# baseband.net
KiCad netlist of a schematic drawn in Altium Designer
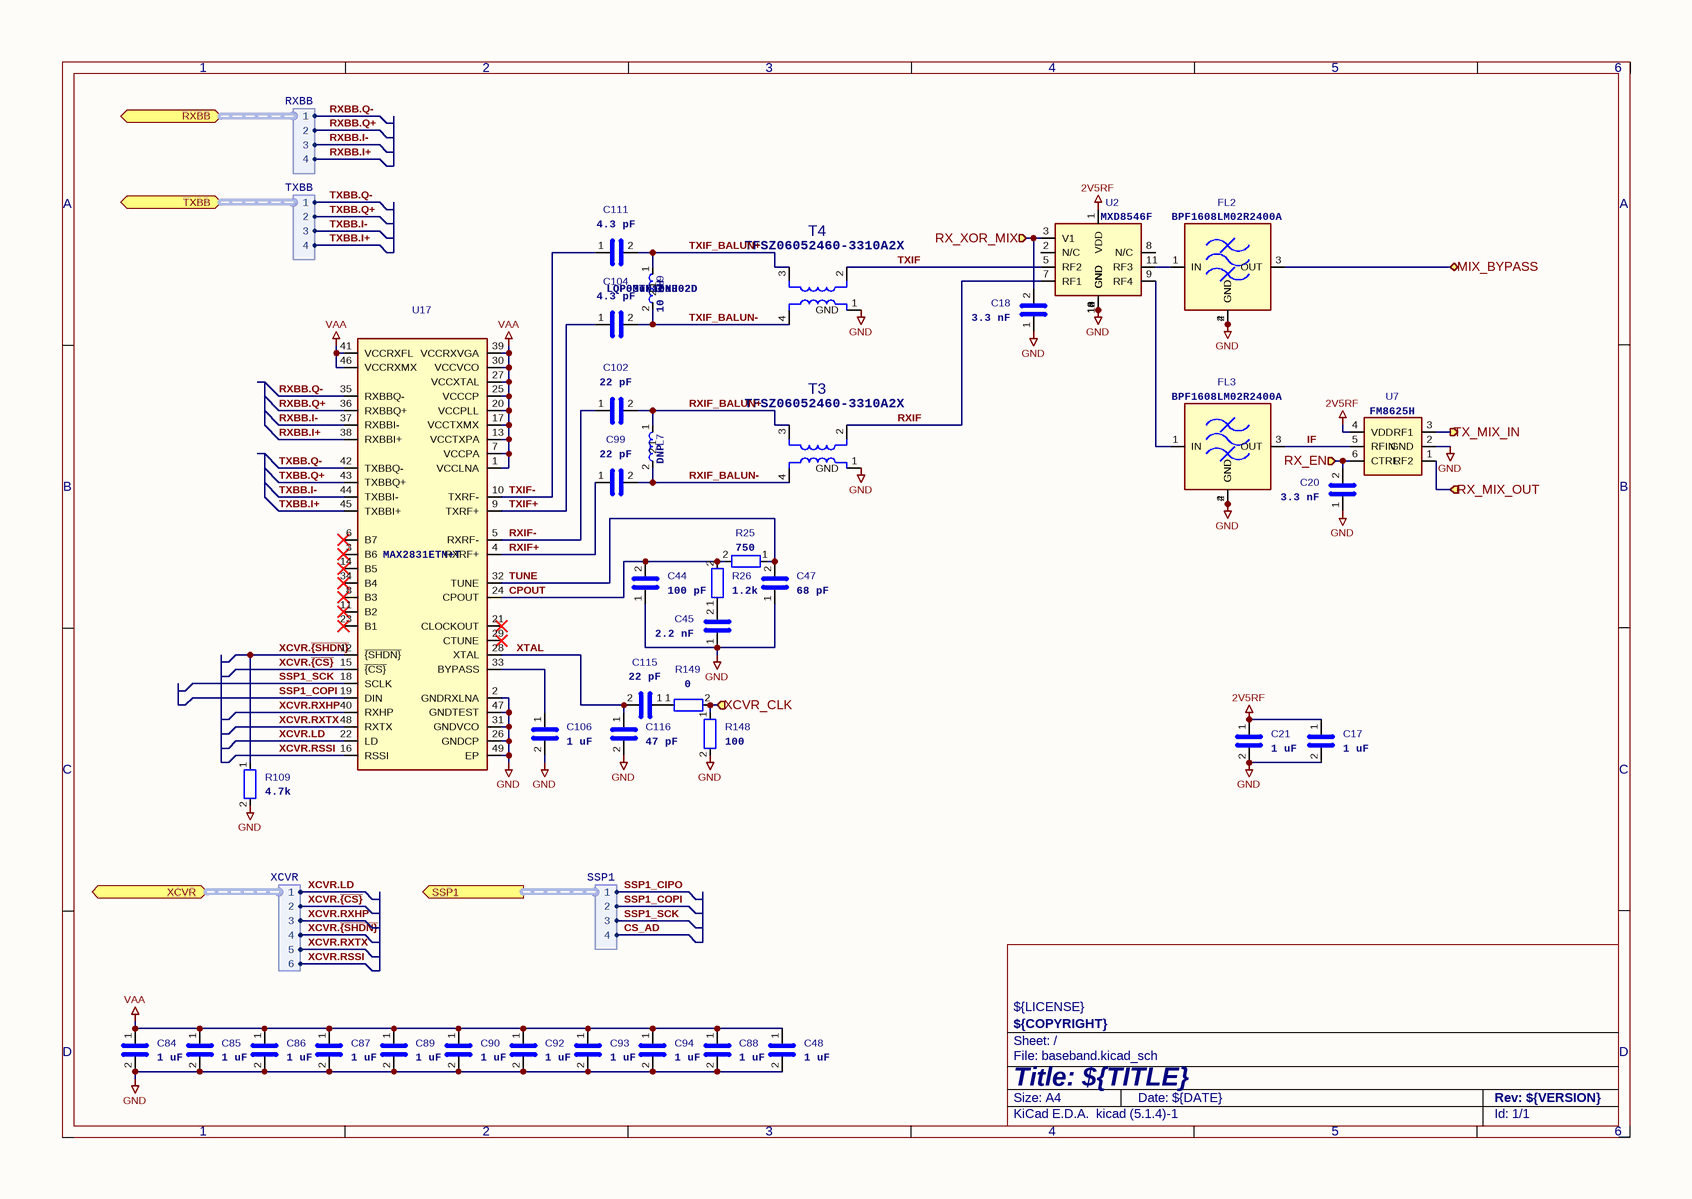
[diagram p0: baseband.SchDoc]

(export (version "E")
  (design (tool "Eeschema 10.0.6"))
  (components
    (comp (ref "C17")
      (value "1 uF")
      (footprint "C_0201_0603Metric")
      (fields (field (name "MANUFACTURER") "Murata") (field (name "PART NUMBER") "GRM033R61A105ME44D"))
      (libsource (lib "Device") (part "C"))
    )
    (comp (ref "C18")
      (value "3.3 nF")
      (footprint "C_0201_0603Metric")
      (fields (field (name "MANUFACTURER") "Murata") (field (name "PART NUMBER") "GRM033R71A332KA01D"))
      (libsource (lib "Device") (part "C"))
    )
    (comp (ref "C20")
      (value "3.3 nF")
      (footprint "C_0201_0603Metric")
      (fields (field (name "MANUFACTURER") "Murata") (field (name "PART NUMBER") "GRM033R71A332KA01D"))
      (libsource (lib "Device") (part "C"))
    )
    (comp (ref "C21")
      (value "1 uF")
      (footprint "C_0201_0603Metric")
      (fields (field (name "MANUFACTURER") "Murata") (field (name "PART NUMBER") "GRM033R61A105ME44D"))
      (libsource (lib "Device") (part "C"))
    )
    (comp (ref "C44")
      (value "100 pF")
      (footprint "C_0201_0603Metric")
      (fields (field (name "MANUFACTURER") "Murata") (field (name "PART NUMBER") "GRM0335C1E101JA01D"))
      (libsource (lib "Device") (part "C"))
    )
    (comp (ref "C45")
      (value "2.2 nF")
      (footprint "C_0201_0603Metric")
      (fields (field (name "MANUFACTURER") "Murata") (field (name "PART NUMBER") "GRM033R71A222KA01D"))
      (libsource (lib "Device") (part "C"))
    )
    (comp (ref "C47")
      (value "68 pF")
      (footprint "C_0201_0603Metric")
      (fields (field (name "MANUFACTURER") "Murata") (field (name "PART NUMBER") "GRM0335C1H680JA01D"))
      (libsource (lib "Device") (part "C"))
    )
    (comp (ref "C48")
      (value "1 uF")
      (footprint "C_0201_0603Metric")
      (fields (field (name "MANUFACTURER") "Murata") (field (name "PART NUMBER") "GRM033R61A105ME44D"))
      (libsource (lib "Device") (part "C"))
    )
    (comp (ref "C84")
      (value "1 uF")
      (footprint "C_0201_0603Metric")
      (fields (field (name "MANUFACTURER") "Murata") (field (name "PART NUMBER") "GRM033R61A105ME44D"))
      (libsource (lib "Device") (part "C"))
    )
    (comp (ref "C85")
      (value "1 uF")
      (footprint "C_0201_0603Metric")
      (fields (field (name "MANUFACTURER") "Murata") (field (name "PART NUMBER") "GRM033R61A105ME44D"))
      (libsource (lib "Device") (part "C"))
    )
    (comp (ref "C86")
      (value "1 uF")
      (footprint "C_0201_0603Metric")
      (fields (field (name "MANUFACTURER") "Murata") (field (name "PART NUMBER") "GRM033R61A105ME44D"))
      (libsource (lib "Device") (part "C"))
    )
    (comp (ref "C87")
      (value "1 uF")
      (footprint "C_0201_0603Metric")
      (fields (field (name "MANUFACTURER") "Murata") (field (name "PART NUMBER") "GRM033R61A105ME44D"))
      (libsource (lib "Device") (part "C"))
    )
    (comp (ref "C88")
      (value "1 uF")
      (footprint "C_0201_0603Metric")
      (fields (field (name "MANUFACTURER") "Murata") (field (name "PART NUMBER") "GRM033R61A105ME44D"))
      (libsource (lib "Device") (part "C"))
    )
    (comp (ref "C89")
      (value "1 uF")
      (footprint "C_0201_0603Metric")
      (fields (field (name "MANUFACTURER") "Murata") (field (name "PART NUMBER") "GRM033R61A105ME44D"))
      (libsource (lib "Device") (part "C"))
    )
    (comp (ref "C90")
      (value "1 uF")
      (footprint "C_0201_0603Metric")
      (fields (field (name "MANUFACTURER") "Murata") (field (name "PART NUMBER") "GRM033R61A105ME44D"))
      (libsource (lib "Device") (part "C"))
    )
    (comp (ref "C92")
      (value "1 uF")
      (footprint "C_0201_0603Metric")
      (fields (field (name "MANUFACTURER") "Murata") (field (name "PART NUMBER") "GRM033R61A105ME44D"))
      (libsource (lib "Device") (part "C"))
    )
    (comp (ref "C93")
      (value "1 uF")
      (footprint "C_0201_0603Metric")
      (fields (field (name "MANUFACTURER") "Murata") (field (name "PART NUMBER") "GRM033R61A105ME44D"))
      (libsource (lib "Device") (part "C"))
    )
    (comp (ref "C94")
      (value "1 uF")
      (footprint "C_0201_0603Metric")
      (fields (field (name "MANUFACTURER") "Murata") (field (name "PART NUMBER") "GRM033R61A105ME44D"))
      (libsource (lib "Device") (part "C"))
    )
    (comp (ref "C99")
      (value "22 pF")
      (footprint "C_0201_0603Metric")
      (fields (field (name "MANUFACTURER") "Murata") (field (name "PART NUMBER") "GRM0335C1H220JA01D"))
      (libsource (lib "Device") (part "C"))
    )
    (comp (ref "C102")
      (value "22 pF")
      (footprint "C_0201_0603Metric")
      (fields (field (name "MANUFACTURER") "Murata") (field (name "PART NUMBER") "GRM0335C1H220JA01D"))
      (libsource (lib "Device") (part "C"))
    )
    (comp (ref "C104")
      (value "4.3 pF")
      (footprint "C_0201_0603Metric")
      (fields (field (name "MANUFACTURER") "Murata") (field (name "PART NUMBER") "GRM0335C1E4R3CA01D"))
      (libsource (lib "Device") (part "C"))
    )
    (comp (ref "C106")
      (value "1 uF")
      (footprint "C_0201_0603Metric")
      (fields (field (name "MANUFACTURER") "Murata") (field (name "PART NUMBER") "GRM033R61A105ME44D"))
      (libsource (lib "Device") (part "C"))
    )
    (comp (ref "C111")
      (value "4.3 pF")
      (footprint "C_0201_0603Metric")
      (fields (field (name "MANUFACTURER") "Murata") (field (name "PART NUMBER") "GRM0335C1E4R3CA01D"))
      (libsource (lib "Device") (part "C"))
    )
    (comp (ref "C115")
      (value "22 pF")
      (footprint "C_0201_0603Metric")
      (fields (field (name "MANUFACTURER") "Murata") (field (name "PART NUMBER") "GRM0335C1H220JA01D"))
      (libsource (lib "Device") (part "C"))
    )
    (comp (ref "C116")
      (value "47 pF")
      (footprint "C_0201_0603Metric")
      (fields (field (name "MANUFACTURER") "Murata") (field (name "PART NUMBER") "GRM0335C1E470JA01D"))
      (libsource (lib "Device") (part "C"))
    )
    (comp (ref "FL2")
      (value "BPF")
      (footprint "Filter_Pulse_BPF1608LM09R5000A")
      (fields
        (field (name "MANUFACTURER") "Pulse Electronics")
        (field (name "PART NUMBER") "BPF1608LM02R2400A")
      )
      (libsource (lib "RF_Filter") (part "BFCN-1445"))
    )
    (comp (ref "FL3")
      (value "BPF")
      (footprint "Filter_Pulse_BPF1608LM09R5000A")
      (fields
        (field (name "MANUFACTURER") "Pulse Electronics")
        (field (name "PART NUMBER") "BPF1608LM02R2400A")
      )
      (libsource (lib "RF_Filter") (part "BFCN-1445"))
    )
    (comp (ref "L7") (value "DNP") (footprint "L_0201_0603Metric") (libsource (lib "Device") (part "L")))
    (comp (ref "L9")
      (value "10 nH")
      (footprint "L_0201_0603Metric")
      (fields
        (field (name "MANUFACTURER") "Murata")
        (field (name "PART NUMBER") "LQP03TN10NJ02D")
        (field (name "SUBSTITUTION") "LQP03TN10NH02D")
      )
      (libsource (lib "Device") (part "L"))
    )
    (comp (ref "R25")
      (value "750")
      (footprint "R_0201_0603Metric")
      (fields (field (name "MANUFACTURER") "Yageo") (field (name "PART NUMBER") "RC0201JR-07750RL"))
      (libsource (lib "Device") (part "R"))
    )
    (comp (ref "R26")
      (value "1.2k")
      (footprint "R_0201_0603Metric")
      (fields (field (name "MANUFACTURER") "Yageo") (field (name "PART NUMBER") "RC0201JR-071K2L"))
      (libsource (lib "") (part "R_1"))
    )
    (comp (ref "R109")
      (value "4.7k")
      (footprint "R_0201_0603Metric")
      (fields (field (name "MANUFACTURER") "Yageo") (field (name "PART NUMBER") "RC0201FR-074K7L"))
      (libsource (lib "Device") (part "R"))
    )
    (comp (ref "R148")
      (value "100")
      (footprint "R_0201_0603Metric")
      (fields (field (name "MANUFACTURER") "Yageo") (field (name "PART NUMBER") "RC0201JR-07100RL"))
      (libsource (lib "Device") (part "R"))
    )
    (comp (ref "R149")
      (value "0")
      (footprint "R_0201_0603Metric")
      (fields (field (name "MANUFACTURER") "Yageo") (field (name "PART NUMBER") "RC0201JR-070RL"))
      (libsource (lib "") (part "R_1"))
    )
    (comp (ref "T3")
      (value "IF_BALUN")
      (footprint "Balun_TDK_TFSZ06052460-3310A2X")
      (fields (field (name "MANUFACTURER") "TDK") (field (name "PART NUMBER") "TFSZ06052460-3310A2X"))
      (libsource (lib "praline") (part "TFSZ06052460-3310A2X"))
    )
    (comp (ref "T4")
      (value "IF_BALUN")
      (footprint "Balun_TDK_TFSZ06052460-3310A2X")
      (fields (field (name "MANUFACTURER") "TDK") (field (name "PART NUMBER") "TFSZ06052460-3310A2X"))
      (libsource (lib "praline") (part "TFSZ06052460-3310A2X"))
    )
    (comp (ref "U2")
      (value "MXD8546F")
      (footprint "QFN-12-1EP_2x2mm_P0.5mm_EP1x1mm")
      (fields (field (name "MANUFACTURER") "Maxscend") (field (name "PART NUMBER") "MXD8546F"))
      (libsource (lib "praline") (part "MXD8546F"))
    )
    (comp (ref "U7")
      (value "FM8625H")
      (footprint "TSLP-6-4_1.1x0.7mm_P0.4mm")
      (fields (field (name "MANUFACTURER") "Shenzhen Fuman") (field (name "PART NUMBER") "FM8625H"))
      (libsource (lib "praline") (part "BGS12P2L6"))
    )
    (comp (ref "U17")
      (value "MAX2831")
      (footprint "QFN-48-1EP_7x7mm_P0.5mm_EP5.6x5.6mm_ThermalVias")
      (fields (field (name "MANUFACTURER") "Maxim") (field (name "PART NUMBER") "MAX2831ETM+T"))
      (libsource (lib "praline") (part "MAX2831"))
    )
  )
  (nets
    (net (code "5") (name "/CPOUT") (class "Default")
      (node (ref "C44") (pin "2") (pinfunction "2_2") (pintype "passive"))
      (node (ref "R25") (pin "2") (pinfunction "2_2") (pintype "passive"))
      (node (ref "R26") (pin "2") (pinfunction "2_2") (pintype "passive"))
      (node (ref "U17") (pin "24") (pinfunction "CPOUT_24") (pintype "passive"))
    )
    (net (code "7") (name "/IF") (class "Default")
      (node (ref "FL3") (pin "3") (pinfunction "OUT_3") (pintype "passive"))
      (node (ref "U7") (pin "5") (pinfunction "RFIN_5") (pintype "passive"))
    )
    (net (code "8") (name "/MIX_BYPASS") (class "Default")
      (node (ref "FL2") (pin "3") (pinfunction "OUT_3") (pintype "passive"))
    )
    (net (code "9") (name "/RXBB.I+") (class "Default")
      (node (ref "U17") (pin "38") (pinfunction "RXBBI+_38") (pintype "passive"))
    )
    (net (code "10") (name "/RXBB.I-") (class "Default")
      (node (ref "U17") (pin "37") (pinfunction "RXBBI-_37") (pintype "passive"))
    )
    (net (code "11") (name "/RXBB.Q+") (class "Default")
      (node (ref "U17") (pin "36") (pinfunction "RXBBQ+_36") (pintype "passive"))
    )
    (net (code "12") (name "/RXBB.Q-") (class "Default")
      (node (ref "U17") (pin "35") (pinfunction "RXBBQ-_35") (pintype "passive"))
    )
    (net (code "13") (name "/RXIF") (class "Default")
      (node (ref "T3") (pin "2") (pinfunction "2_2") (pintype "passive"))
      (node (ref "U2") (pin "7") (pinfunction "RF1_7") (pintype "passive"))
    )
    (net (code "14") (name "/RXIF+") (class "Default")
      (node (ref "C99") (pin "1") (pinfunction "1_1") (pintype "passive"))
      (node (ref "U17") (pin "4") (pinfunction "RXRF+_4") (pintype "passive"))
    )
    (net (code "15") (name "/RXIF-") (class "Default")
      (node (ref "C102") (pin "1") (pinfunction "1_1") (pintype "passive"))
      (node (ref "U17") (pin "5") (pinfunction "RXRF-_5") (pintype "passive"))
    )
    (net (code "16") (name "/RXIF_BALUN+") (class "Default")
      (node (ref "C102") (pin "2") (pinfunction "2_2") (pintype "passive"))
      (node (ref "L7") (pin "1") (pinfunction "1_1") (pintype "passive"))
      (node (ref "T3") (pin "3") (pinfunction "3_3") (pintype "passive"))
    )
    (net (code "17") (name "/RXIF_BALUN-") (class "Default")
      (node (ref "C99") (pin "2") (pinfunction "2_2") (pintype "passive"))
      (node (ref "L7") (pin "2") (pinfunction "2_2") (pintype "passive"))
      (node (ref "T3") (pin "4") (pinfunction "4_4") (pintype "passive"))
    )
    (net (code "18") (name "/RX_EN") (class "Default")
      (node (ref "C20") (pin "2") (pinfunction "2_2") (pintype "passive"))
      (node (ref "U7") (pin "6") (pinfunction "CTRL_6") (pintype "passive"))
    )
    (net (code "19") (name "/RX_MIX_OUT") (class "Default")
      (node (ref "U7") (pin "1") (pinfunction "RF2_1") (pintype "passive"))
    )
    (net (code "20") (name "/RX_XOR_MIX") (class "Default")
      (node (ref "C18") (pin "2") (pinfunction "2_2") (pintype "passive"))
      (node (ref "U2") (pin "3") (pinfunction "V1_3") (pintype "passive"))
    )
    (net (code "22") (name "/SSP1_COPI") (class "Default")
      (node (ref "U17") (pin "19") (pinfunction "DIN_19") (pintype "passive"))
    )
    (net (code "23") (name "/SSP1_SCK") (class "Default")
      (node (ref "U17") (pin "18") (pinfunction "SCLK_18") (pintype "passive"))
    )
    (net (code "24") (name "/TUNE") (class "Default")
      (node (ref "C47") (pin "2") (pinfunction "2_2") (pintype "passive"))
      (node (ref "R25") (pin "1") (pinfunction "1_1") (pintype "passive"))
      (node (ref "U17") (pin "32") (pinfunction "TUNE_32") (pintype "passive"))
    )
    (net (code "25") (name "/TXBB.I+") (class "Default")
      (node (ref "U17") (pin "45") (pinfunction "TXBBI+_45") (pintype "passive"))
    )
    (net (code "26") (name "/TXBB.I-") (class "Default")
      (node (ref "U17") (pin "44") (pinfunction "TXBBI-_44") (pintype "passive"))
    )
    (net (code "27") (name "/TXBB.Q+") (class "Default")
      (node (ref "U17") (pin "43") (pinfunction "TXBBQ+_43") (pintype "passive"))
    )
    (net (code "28") (name "/TXBB.Q-") (class "Default")
      (node (ref "U17") (pin "42") (pinfunction "TXBBQ-_42") (pintype "passive"))
    )
    (net (code "29") (name "/TXIF") (class "Default")
      (node (ref "T4") (pin "2") (pinfunction "2_2") (pintype "passive"))
      (node (ref "U2") (pin "5") (pinfunction "RF2_5") (pintype "passive"))
    )
    (net (code "30") (name "/TXIF+") (class "Default")
      (node (ref "C104") (pin "1") (pinfunction "1_1") (pintype "passive"))
      (node (ref "U17") (pin "9") (pinfunction "TXRF+_9") (pintype "passive"))
    )
    (net (code "31") (name "/TXIF-") (class "Default")
      (node (ref "C111") (pin "1") (pinfunction "1_1") (pintype "passive"))
      (node (ref "U17") (pin "10") (pinfunction "TXRF-_10") (pintype "passive"))
    )
    (net (code "32") (name "/TXIF_BALUN+") (class "Default")
      (node (ref "C111") (pin "2") (pinfunction "2_2") (pintype "passive"))
      (node (ref "L9") (pin "1") (pinfunction "1_1") (pintype "passive"))
      (node (ref "T4") (pin "3") (pinfunction "3_3") (pintype "passive"))
    )
    (net (code "33") (name "/TXIF_BALUN-") (class "Default")
      (node (ref "C104") (pin "2") (pinfunction "2_2") (pintype "passive"))
      (node (ref "L9") (pin "2") (pinfunction "2_2") (pintype "passive"))
      (node (ref "T4") (pin "4") (pinfunction "4_4") (pintype "passive"))
    )
    (net (code "34") (name "/TX_MIX_IN") (class "Default")
      (node (ref "U7") (pin "3") (pinfunction "RF1_3") (pintype "passive"))
    )
    (net (code "35") (name "/XCVR.LD") (class "Default")
      (node (ref "U17") (pin "22") (pinfunction "LD_22") (pintype "passive"))
    )
    (net (code "36") (name "/XCVR.RSSI") (class "Default")
      (node (ref "U17") (pin "16") (pinfunction "RSSI_16") (pintype "passive"))
    )
    (net (code "37") (name "/XCVR.RXHP") (class "Default")
      (node (ref "U17") (pin "40") (pinfunction "RXHP_40") (pintype "passive"))
    )
    (net (code "38") (name "/XCVR.RXTX") (class "Default")
      (node (ref "U17") (pin "48") (pinfunction "RXTX_48") (pintype "passive"))
    )
    (net (code "39") (name "/XCVR.~{{CS}}") (class "Default")
      (node (ref "U17") (pin "15") (pinfunction "~{{CS}}_15") (pintype "passive"))
    )
    (net (code "40") (name "/XCVR.~{{SHDN}}") (class "Default")
      (node (ref "R109") (pin "1") (pinfunction "1_1") (pintype "passive"))
      (node (ref "U17") (pin "12") (pinfunction "~{{SHDN}}_12") (pintype "passive"))
    )
    (net (code "41") (name "/XCVR_CLK") (class "Default")
      (node (ref "R148") (pin "1") (pinfunction "1_1") (pintype "passive"))
      (node (ref "R149") (pin "2") (pinfunction "2_2") (pintype "passive"))
    )
    (net (code "42") (name "/XTAL") (class "Default")
      (node (ref "C115") (pin "2") (pinfunction "2_2") (pintype "passive"))
      (node (ref "C116") (pin "1") (pinfunction "1_1") (pintype "passive"))
      (node (ref "U17") (pin "28") (pinfunction "XTAL_28") (pintype "passive"))
    )
    (net (code "47") (name "2V5RF") (class "Default")
      (node (ref "C17") (pin "1") (pinfunction "1_1") (pintype "passive"))
      (node (ref "C21") (pin "1") (pinfunction "1_1") (pintype "passive"))
      (node (ref "U2") (pin "1") (pinfunction "VDD_1") (pintype "passive"))
      (node (ref "U7") (pin "4") (pinfunction "VDD_4") (pintype "passive"))
    )
    (net (code "48") (name "GND") (class "Default")
      (node (ref "C106") (pin "2") (pinfunction "2_2") (pintype "passive"))
      (node (ref "C116") (pin "2") (pinfunction "2_2") (pintype "passive"))
      (node (ref "C17") (pin "2") (pinfunction "2_2") (pintype "passive"))
      (node (ref "C18") (pin "1") (pinfunction "1_1") (pintype "passive"))
      (node (ref "C20") (pin "1") (pinfunction "1_1") (pintype "passive"))
      (node (ref "C21") (pin "2") (pinfunction "2_2") (pintype "passive"))
      (node (ref "C44") (pin "1") (pinfunction "1_1") (pintype "passive"))
      (node (ref "C45") (pin "1") (pinfunction "1_1") (pintype "passive"))
      (node (ref "C47") (pin "1") (pinfunction "1_1") (pintype "passive"))
      (node (ref "C48") (pin "2") (pinfunction "2_2") (pintype "passive"))
      (node (ref "C84") (pin "2") (pinfunction "2_2") (pintype "passive"))
      (node (ref "C85") (pin "2") (pinfunction "2_2") (pintype "passive"))
      (node (ref "C86") (pin "2") (pinfunction "2_2") (pintype "passive"))
      (node (ref "C87") (pin "2") (pinfunction "2_2") (pintype "passive"))
      (node (ref "C88") (pin "2") (pinfunction "2_2") (pintype "passive"))
      (node (ref "C89") (pin "2") (pinfunction "2_2") (pintype "passive"))
      (node (ref "C90") (pin "2") (pinfunction "2_2") (pintype "passive"))
      (node (ref "C92") (pin "2") (pinfunction "2_2") (pintype "passive"))
      (node (ref "C93") (pin "2") (pinfunction "2_2") (pintype "passive"))
      (node (ref "C94") (pin "2") (pinfunction "2_2") (pintype "passive"))
      (node (ref "FL2") (pin "2") (pinfunction "GND_2") (pintype "passive"))
      (node (ref "FL2") (pin "4") (pinfunction "GND_4") (pintype "passive"))
      (node (ref "FL3") (pin "2") (pinfunction "GND_2") (pintype "passive"))
      (node (ref "FL3") (pin "4") (pinfunction "GND_4") (pintype "passive"))
      (node (ref "R109") (pin "2") (pinfunction "2_2") (pintype "passive"))
      (node (ref "R148") (pin "2") (pinfunction "2_2") (pintype "passive"))
      (node (ref "T3") (pin "1") (pinfunction "GND_1") (pintype "passive"))
      (node (ref "T4") (pin "1") (pinfunction "GND_1") (pintype "passive"))
      (node (ref "U17") (pin "2") (pinfunction "GNDRXLNA_2") (pintype "passive"))
      (node (ref "U17") (pin "26") (pinfunction "GNDCP_26") (pintype "passive"))
      (node (ref "U17") (pin "31") (pinfunction "GNDVCO_31") (pintype "passive"))
      (node (ref "U17") (pin "47") (pinfunction "GNDTEST_47") (pintype "passive"))
      (node (ref "U17") (pin "49") (pinfunction "EP_49") (pintype "passive"))
      (node (ref "U2") (pin "10") (pinfunction "GND_10") (pintype "passive"))
      (node (ref "U2") (pin "12") (pinfunction "GND_12") (pintype "passive"))
      (node (ref "U2") (pin "13") (pinfunction "GND_13") (pintype "passive"))
      (node (ref "U2") (pin "4") (pinfunction "GND_4") (pintype "passive"))
      (node (ref "U2") (pin "6") (pinfunction "GND_6") (pintype "passive"))
      (node (ref "U7") (pin "2") (pinfunction "GND_2") (pintype "passive"))
    )
    (net (code "49") (name "Net-(C45-Pad2)") (class "Default")
      (node (ref "C45") (pin "2") (pinfunction "2_2") (pintype "passive"))
      (node (ref "R26") (pin "1") (pinfunction "1_1") (pintype "passive"))
    )
    (net (code "50") (name "Net-(C115-Pad1)") (class "Default")
      (node (ref "C115") (pin "1") (pinfunction "1_1") (pintype "passive"))
      (node (ref "R149") (pin "1") (pinfunction "1_1") (pintype "passive"))
    )
    (net (code "51") (name "Net-(FL2-IN)") (class "Default")
      (node (ref "FL2") (pin "1") (pinfunction "IN_1") (pintype "passive"))
      (node (ref "U2") (pin "11") (pinfunction "RF3_11") (pintype "passive"))
    )
    (net (code "52") (name "Net-(FL3-IN)") (class "Default")
      (node (ref "FL3") (pin "1") (pinfunction "IN_1") (pintype "passive"))
      (node (ref "U2") (pin "9") (pinfunction "RF4_9") (pintype "passive"))
    )
    (net (code "53") (name "Net-(U17-BYPASS)") (class "Default")
      (node (ref "C106") (pin "1") (pinfunction "1_1") (pintype "passive"))
      (node (ref "U17") (pin "33") (pinfunction "BYPASS_33") (pintype "passive"))
    )
    (net (code "54") (name "VAA") (class "Default")
      (node (ref "C48") (pin "1") (pinfunction "1_1") (pintype "passive"))
      (node (ref "C84") (pin "1") (pinfunction "1_1") (pintype "passive"))
      (node (ref "C85") (pin "1") (pinfunction "1_1") (pintype "passive"))
      (node (ref "C86") (pin "1") (pinfunction "1_1") (pintype "passive"))
      (node (ref "C87") (pin "1") (pinfunction "1_1") (pintype "passive"))
      (node (ref "C88") (pin "1") (pinfunction "1_1") (pintype "passive"))
      (node (ref "C89") (pin "1") (pinfunction "1_1") (pintype "passive"))
      (node (ref "C90") (pin "1") (pinfunction "1_1") (pintype "passive"))
      (node (ref "C92") (pin "1") (pinfunction "1_1") (pintype "passive"))
      (node (ref "C93") (pin "1") (pinfunction "1_1") (pintype "passive"))
      (node (ref "C94") (pin "1") (pinfunction "1_1") (pintype "passive"))
      (node (ref "U17") (pin "1") (pinfunction "VCCLNA_1") (pintype "passive"))
      (node (ref "U17") (pin "13") (pinfunction "VCCTXPA_13") (pintype "passive"))
      (node (ref "U17") (pin "17") (pinfunction "VCCTXMX_17") (pintype "passive"))
      (node (ref "U17") (pin "20") (pinfunction "VCCPLL_20") (pintype "passive"))
      (node (ref "U17") (pin "25") (pinfunction "VCCCP_25") (pintype "passive"))
      (node (ref "U17") (pin "27") (pinfunction "VCCXTAL_27") (pintype "passive"))
      (node (ref "U17") (pin "30") (pinfunction "VCCVCO_30") (pintype "passive"))
      (node (ref "U17") (pin "39") (pinfunction "VCCRXVGA_39") (pintype "passive"))
      (node (ref "U17") (pin "41") (pinfunction "VCCRXFL_41") (pintype "passive"))
      (node (ref "U17") (pin "46") (pinfunction "VCCRXMX_46") (pintype "passive"))
      (node (ref "U17") (pin "7") (pinfunction "VCCPA_7") (pintype "passive"))
    )
    (net (code "55") (name "unconnected-(U2-N{slash}C-Pad2)") (class "Default")
      (node (ref "U2") (pin "2") (pinfunction "N/C_2") (pintype "passive"))
    )
    (net (code "56") (name "unconnected-(U2-N{slash}C-Pad8)") (class "Default")
      (node (ref "U2") (pin "8") (pinfunction "N/C_8") (pintype "passive"))
    )
    (net (code "57") (name "unconnected-(U17-B1-Pad23)") (class "Default")
      (node (ref "U17") (pin "23") (pinfunction "B1_23") (pintype "passive+no_connect"))
    )
    (net (code "58") (name "unconnected-(U17-B2-Pad11)") (class "Default")
      (node (ref "U17") (pin "11") (pinfunction "B2_11") (pintype "passive+no_connect"))
    )
    (net (code "59") (name "unconnected-(U17-B3-Pad8)") (class "Default")
      (node (ref "U17") (pin "8") (pinfunction "B3_8") (pintype "passive+no_connect"))
    )
    (net (code "60") (name "unconnected-(U17-B4-Pad34)") (class "Default")
      (node (ref "U17") (pin "34") (pinfunction "B4_34") (pintype "passive+no_connect"))
    )
    (net (code "61") (name "unconnected-(U17-B5-Pad14)") (class "Default")
      (node (ref "U17") (pin "14") (pinfunction "B5_14") (pintype "passive+no_connect"))
    )
    (net (code "62") (name "unconnected-(U17-B6-Pad3)") (class "Default")
      (node (ref "U17") (pin "3") (pinfunction "B6_3") (pintype "passive+no_connect"))
    )
    (net (code "63") (name "unconnected-(U17-B7-Pad6)") (class "Default")
      (node (ref "U17") (pin "6") (pinfunction "B7_6") (pintype "passive+no_connect"))
    )
    (net (code "64") (name "unconnected-(U17-CLOCKOUT-Pad21)") (class "Default")
      (node (ref "U17") (pin "21") (pinfunction "CLOCKOUT_21") (pintype "passive+no_connect"))
    )
    (net (code "65") (name "unconnected-(U17-CTUNE-Pad29)") (class "Default")
      (node (ref "U17") (pin "29") (pinfunction "CTUNE_29") (pintype "passive+no_connect"))
    )
  )
)
